# USB.net
KiCad netlist of a schematic drawn in Altium Designer
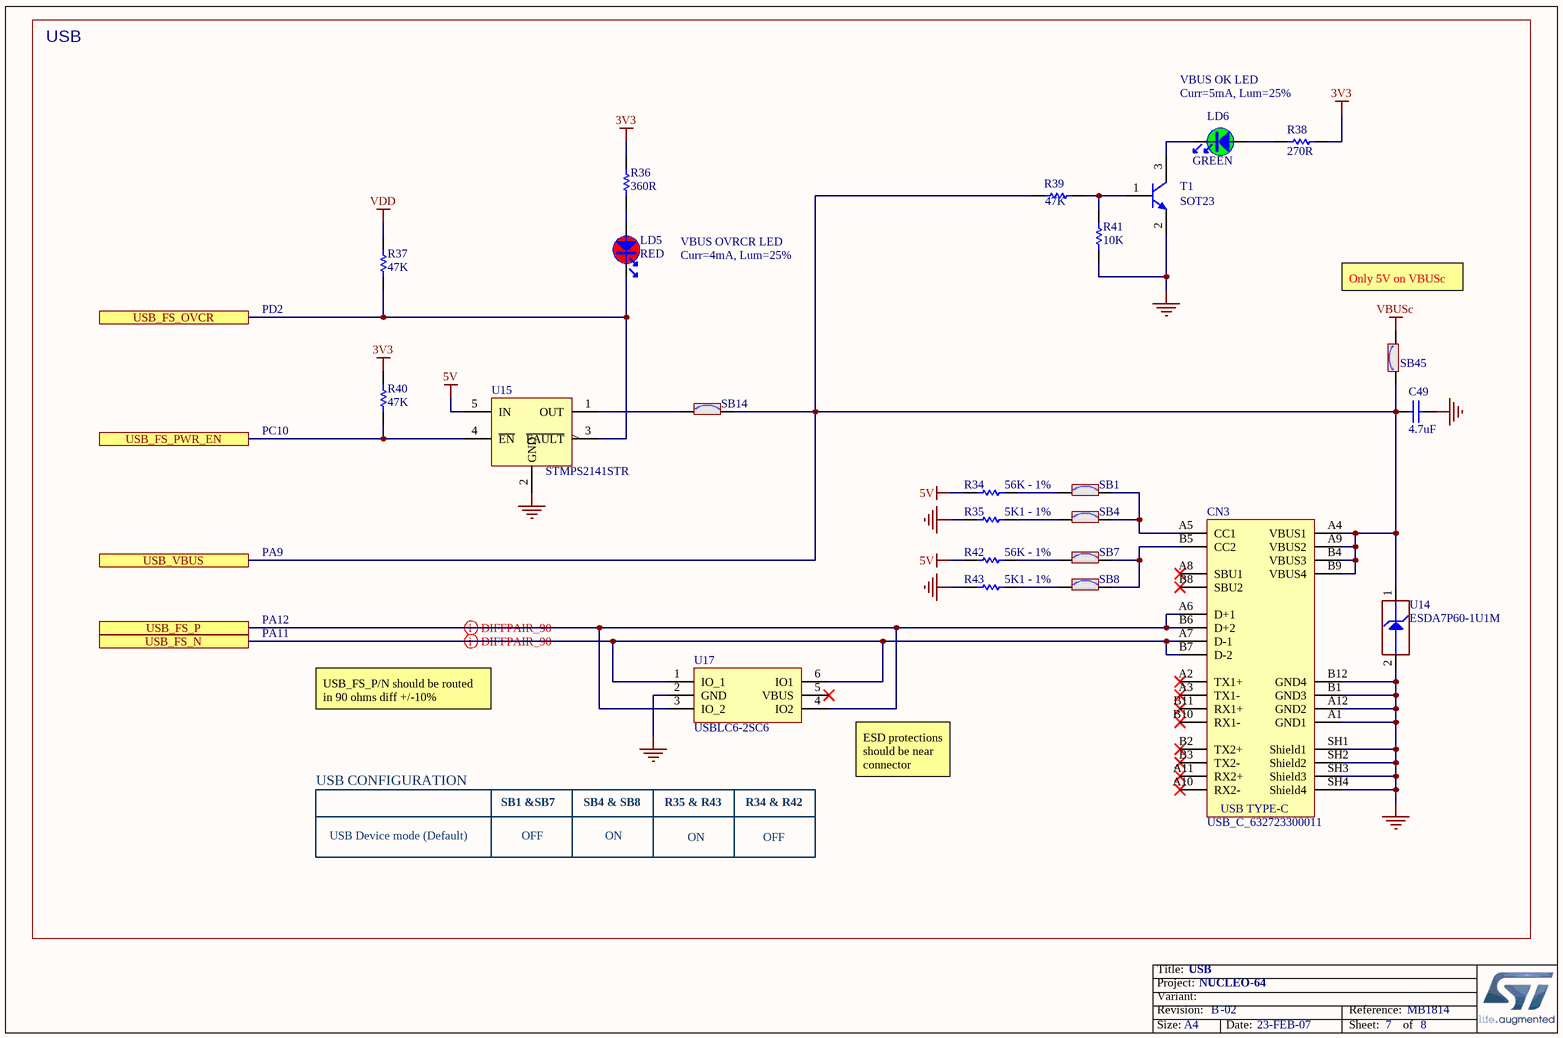
[diagram p0: USB.SchDoc]

(export (version "E")
  (design (tool "Eeschema 10.0.6"))
  (components
    (comp (ref "C49")
      (value "4.7uF")
      (footprint "C0603")
      (description "Capacitor, MLCC, 4.7uF, 16V, X5R, 10%, 0603, T=0.8mm")
      (fields
        (field (name "INTERNAL_PART_NUMBER") "MCD-00009")
        (field (name "MANUFACTURER_PART_NUMBER") "CC0603KRX5R7BB475")
        (field (name "PROVIDED_BY") "SUBCO")
      )
      (libsource (lib "MCD_PARTS_database") (part "Capacitor"))
    )
    (comp (ref "CN3")
      (value "USB_C_632723300011")
      (footprint "CON_USB-TYPEC_WE_632723300011")
      (description "USB_TypeC, 24pins, RA, TH, T=1.9mm (USB certified)")
      (fields
        (field (name "INTERNAL_PART_NUMBER") "MCD-02273")
        (field (name "MANUFACTURER") "WURTH ELEKTRONIK")
      )
      (libsource (lib "MCD_PARTS_database") (part "USB_TYPE_C_Receptacle"))
    )
    (comp (ref "LD5")
      (value "RED")
      (footprint "LED_0603_VISHAY_VLMS1300-GS08_RED_1A2K_H0P8")
      (description "LED Red, 0603 SMD, 2V Forward Voltage")
      (fields
        (field (name "INTERNAL_PART_NUMBER") "MCD-00587")
        (field (name "MANUFACTURER_PART_NUMBER") "VLMS1300-GS08")
        (field (name "PROVIDED_BY") "SUBCO")
      )
      (libsource (lib "MCD_PARTS_database") (part "LED_red"))
    )
    (comp (ref "LD6")
      (value "GREEN")
      (footprint "LED_0603_OSRAM_LG-Q396-PS-35_GREEN_1A2K_H0P4")
      (description "LED Green, 0603 SMD, Forward Voltage Typ=2V, Max=2.5V")
      (fields
        (field (name "INTERNAL_PART_NUMBER") "MCD-00588")
        (field (name "MANUFACTURER_PART_NUMBER") "LG Q396-PS-35")
        (field (name "PROVIDED_BY") "SUBCO")
      )
      (libsource (lib "MCD_PARTS_database") (part "LED_green"))
    )
    (comp (ref "R34")
      (value "56K - 1%")
      (footprint "R0603")
      (description "Resistor, 56K, 0603, +/-1%, 1/10W")
      (fields (field (name "INTERNAL_PART_NUMBER") "MCD-00494") (field (name "MANUFACTURER") "YAGEO"))
      (libsource (lib "MCD_PARTS_database") (part "Resistor"))
    )
    (comp (ref "R35")
      (value "5K1 - 1%")
      (footprint "R0603")
      (description "Resistor, 5K1, 0603, +/-1%, 1/10W")
      (fields (field (name "INTERNAL_PART_NUMBER") "MCD-00334") (field (name "MANUFACTURER") "YAGEO"))
      (libsource (lib "MCD_PARTS_database") (part "Resistor"))
    )
    (comp (ref "R36")
      (value "360R")
      (footprint "R0402")
      (description "Resistor,360R,0402,1%,1/16W")
      (fields
        (field (name "INTERNAL_PART_NUMBER") "MCD-00461")
        (field (name "MANUFACTURER_PART_NUMBER") "RC0402FR-07360RL")
        (field (name "PROVIDED_BY") "SUBCO")
      )
      (libsource (lib "MCD_PARTS_database") (part "Resistor"))
    )
    (comp (ref "R37")
      (value "47K")
      (footprint "R0402")
      (description "Resistor,47K,0402,1%,1/16W")
      (fields
        (field (name "INTERNAL_PART_NUMBER") "MCD-00063")
        (field (name "MANUFACTURER_PART_NUMBER") "RC0402FR-0747KL")
        (field (name "PROVIDED_BY") "SUBCO")
      )
      (libsource (lib "MCD_PARTS_database") (part "Resistor"))
    )
    (comp (ref "R38")
      (value "270R")
      (footprint "R0402")
      (description "Resistor,270R,0402,1%,1/16W")
      (fields
        (field (name "INTERNAL_PART_NUMBER") "MCD-00441")
        (field (name "MANUFACTURER_PART_NUMBER") "RC0402FR-07270RL")
        (field (name "PROVIDED_BY") "SUBCO")
      )
      (libsource (lib "MCD_PARTS_database") (part "Resistor"))
    )
    (comp (ref "R39")
      (value "47K")
      (footprint "R0402")
      (description "Resistor,47K,0402,1%,1/16W")
      (fields
        (field (name "INTERNAL_PART_NUMBER") "MCD-00063")
        (field (name "MANUFACTURER_PART_NUMBER") "RC0402FR-0747KL")
        (field (name "PROVIDED_BY") "SUBCO")
      )
      (libsource (lib "MCD_PARTS_database") (part "Resistor"))
    )
    (comp (ref "R40")
      (value "47K")
      (footprint "R0402")
      (description "Resistor,47K,0402,1%,1/16W")
      (fields
        (field (name "INTERNAL_PART_NUMBER") "MCD-00063")
        (field (name "MANUFACTURER_PART_NUMBER") "RC0402FR-0747KL")
        (field (name "PROVIDED_BY") "SUBCO")
      )
      (libsource (lib "MCD_PARTS_database") (part "Resistor"))
    )
    (comp (ref "R41")
      (value "10K")
      (footprint "R0402")
      (description "Resistor,10K,0402,1%,1/16W")
      (fields
        (field (name "INTERNAL_PART_NUMBER") "MCD-00053")
        (field (name "MANUFACTURER_PART_NUMBER") "RC0402FR-0710KL")
        (field (name "PROVIDED_BY") "SUBCO")
      )
      (libsource (lib "MCD_PARTS_database") (part "Resistor"))
    )
    (comp (ref "R42")
      (value "56K - 1%")
      (footprint "R0603")
      (description "Resistor, 56K, 0603, +/-1%, 1/10W")
      (fields (field (name "INTERNAL_PART_NUMBER") "MCD-00494") (field (name "MANUFACTURER") "YAGEO"))
      (libsource (lib "MCD_PARTS_database") (part "Resistor"))
    )
    (comp (ref "R43")
      (value "5K1 - 1%")
      (footprint "R0603")
      (description "Resistor, 5K1, 0603, +/-1%, 1/10W")
      (fields (field (name "INTERNAL_PART_NUMBER") "MCD-00334") (field (name "MANUFACTURER") "YAGEO"))
      (libsource (lib "MCD_PARTS_database") (part "Resistor"))
    )
    (comp (ref "SB1")
      (value "~")
      (footprint "SOLDER-BRIDGE_R0603-0R")
      (description "Solder Bridge ON")
      (fields
        (field (name "INTERNAL_PART_NUMBER") "MCD-00071")
        (field (name "MANUFACTURER_PART_NUMBER") "RC0603JR-070RL")
        (field (name "PROVIDED_BY") "SUBCO")
      )
      (libsource (lib "") (part "SB_ON_1"))
    )
    (comp (ref "SB4")
      (value "~")
      (footprint "SOLDER-BRIDGE_R0603-0R")
      (description "Solder Bridge ON")
      (fields
        (field (name "INTERNAL_PART_NUMBER") "MCD-00071")
        (field (name "MANUFACTURER_PART_NUMBER") "RC0603JR-070RL")
        (field (name "PROVIDED_BY") "SUBCO")
      )
      (libsource (lib "") (part "SB_ON_1"))
    )
    (comp (ref "SB7")
      (value "~")
      (footprint "SOLDER-BRIDGE_R0603-0R")
      (description "Solder Bridge ON")
      (fields
        (field (name "INTERNAL_PART_NUMBER") "MCD-00071")
        (field (name "MANUFACTURER_PART_NUMBER") "RC0603JR-070RL")
        (field (name "PROVIDED_BY") "SUBCO")
      )
      (libsource (lib "") (part "SB_ON_1"))
    )
    (comp (ref "SB8")
      (value "~")
      (footprint "SOLDER-BRIDGE_R0603-0R")
      (description "Solder Bridge ON")
      (fields
        (field (name "INTERNAL_PART_NUMBER") "MCD-00071")
        (field (name "MANUFACTURER_PART_NUMBER") "RC0603JR-070RL")
        (field (name "PROVIDED_BY") "SUBCO")
      )
      (libsource (lib "") (part "SB_ON_1"))
    )
    (comp (ref "SB14")
      (value "~")
      (footprint "SOLDER-BRIDGE_R0603-0R")
      (description "Solder Bridge ON")
      (fields
        (field (name "INTERNAL_PART_NUMBER") "MCD-00071")
        (field (name "MANUFACTURER_PART_NUMBER") "RC0603JR-070RL")
        (field (name "PROVIDED_BY") "SUBCO")
      )
      (libsource (lib "") (part "SB_ON_1"))
    )
    (comp (ref "SB45")
      (value "~")
      (footprint "SOLDER-BRIDGE_R0603-0R")
      (description "Solder Bridge ON")
      (fields
        (field (name "INTERNAL_PART_NUMBER") "MCD-00071")
        (field (name "MANUFACTURER_PART_NUMBER") "RC0603JR-070RL")
        (field (name "PROVIDED_BY") "SUBCO")
      )
      (libsource (lib "MCD_PARTS_database") (part "SB_ON"))
    )
    (comp (ref "T1")
      (value "SOT23")
      (footprint "NPN_SOT23")
      (description "NPN Bipolar Transistor")
      (fields
        (field (name "INTERNAL_PART_NUMBER") "MCD-00073")
        (field (name "MANUFACTURER_PART_NUMBER") "BSR14")
        (field (name "PROVIDED_BY") "SUBCO")
      )
      (libsource (lib "MCD_PARTS_database") (part "9013-SOT23"))
    )
    (comp (ref "U14")
      (value "ESDA7P60-1U1M")
      (footprint "ESD_QFN2_1P6X1_P125")
      (description "High power transient voltage suppressor, 7V breakdown")
      (fields (field (name "INTERNAL_PART_NUMBER") "MCD-00251") (field (name "BMS_PART_NUMBER") "9179042"))
      (libsource (lib "MCD_PARTS_database") (part "ESD-TRANSIL"))
    )
    (comp (ref "U15")
      (value "STMPS2141STR")
      (footprint "MOS_SOT23-5L")
      (description "Enhanced single channel power switches with active low enable pin")
      (fields
        (field (name "INTERNAL_PART_NUMBER") "MCD-00083")
        (field (name "MANUFACTURER") "STMICROELECTRONICS")
        (field (name "PROVIDED_BY") "SUBCO with ST control")
      )
      (libsource (lib "MCD_PARTS_database") (part "STMPS2141STR"))
    )
    (comp (ref "U17")
      (value "USBLC6-2SC6")
      (footprint "ESD_SOT23-6L")
      (description "Very low capacitance ESD protection")
      (fields
        (field (name "INTERNAL_PART_NUMBER") "MCD-00163")
        (field (name "MANUFACTURER") "STMICROELECTRONICS")
        (field (name "PROVIDED_BY") "SUBCO with ST control")
      )
      (libsource (lib "MCD_PARTS_database") (part "USBLC6-2SC6"))
    )
  )
  (nets
    (net (code "1") (name "/USB_FS_N") (class "Default")
      (node (ref "CN3") (pin "A7") (pinfunction "D-1_A7") (pintype "passive"))
      (node (ref "CN3") (pin "B7") (pinfunction "D-2_B7") (pintype "passive"))
      (node (ref "U17") (pin "1") (pinfunction "IO_1_1") (pintype "passive"))
      (node (ref "U17") (pin "6") (pinfunction "IO1_6") (pintype "passive"))
    )
    (net (code "2") (name "/USB_FS_OVCR") (class "Default")
      (node (ref "LD5") (pin "2") (pintype "passive"))
      (node (ref "R37") (pin "2") (pinfunction "2_2") (pintype "passive"))
      (node (ref "U15") (pin "3") (pinfunction "~{FAULT}_3") (pintype "passive"))
    )
    (net (code "3") (name "/USB_FS_P") (class "Default")
      (node (ref "CN3") (pin "A6") (pinfunction "D+1_A6") (pintype "passive"))
      (node (ref "CN3") (pin "B6") (pinfunction "D+2_B6") (pintype "passive"))
      (node (ref "U17") (pin "3") (pinfunction "IO_2_3") (pintype "passive"))
      (node (ref "U17") (pin "4") (pinfunction "IO2_4") (pintype "passive"))
    )
    (net (code "4") (name "/USB_FS_PWR_EN") (class "Default")
      (node (ref "R40") (pin "2") (pinfunction "2_2") (pintype "passive"))
      (node (ref "U15") (pin "4") (pinfunction "~{EN}_4") (pintype "passive"))
    )
    (net (code "5") (name "/USB_VBUS") (class "Default")
      (node (ref "C49") (pin "2") (pinfunction "2_2") (pintype "passive"))
      (node (ref "CN3") (pin "A4") (pinfunction "VBUS1_A4") (pintype "passive"))
      (node (ref "CN3") (pin "A9") (pinfunction "VBUS2_A9") (pintype "passive"))
      (node (ref "CN3") (pin "B4") (pinfunction "VBUS3_B4") (pintype "passive"))
      (node (ref "CN3") (pin "B9") (pinfunction "VBUS4_B9") (pintype "passive"))
      (node (ref "R39") (pin "1") (pinfunction "1_1") (pintype "passive"))
      (node (ref "SB14") (pin "2") (pinfunction "2_2") (pintype "passive"))
      (node (ref "SB45") (pin "1") (pinfunction "1_1") (pintype "passive"))
      (node (ref "U14") (pin "1") (pinfunction "IO1_1") (pintype "passive"))
    )
    (net (code "6") (name "3V3") (class "Default")
      (node (ref "R36") (pin "2") (pinfunction "2_2") (pintype "passive"))
      (node (ref "R38") (pin "2") (pinfunction "2_2") (pintype "passive"))
      (node (ref "R40") (pin "1") (pinfunction "1_1") (pintype "passive"))
    )
    (net (code "7") (name "5V") (class "Default")
      (node (ref "R34") (pin "1") (pinfunction "1_1") (pintype "passive"))
      (node (ref "R42") (pin "1") (pinfunction "1_1") (pintype "passive"))
      (node (ref "U15") (pin "5") (pinfunction "IN_5") (pintype "passive"))
    )
    (net (code "8") (name "GND") (class "Default")
      (node (ref "C49") (pin "1") (pinfunction "1_1") (pintype "passive"))
      (node (ref "CN3") (pin "A1") (pinfunction "GND1_A1") (pintype "passive"))
      (node (ref "CN3") (pin "A12") (pinfunction "GND2_A12") (pintype "passive"))
      (node (ref "CN3") (pin "B1") (pinfunction "GND3_B1") (pintype "passive"))
      (node (ref "CN3") (pin "B12") (pinfunction "GND4_B12") (pintype "passive"))
      (node (ref "CN3") (pin "SH1") (pinfunction "Shield1_SH1") (pintype "passive"))
      (node (ref "CN3") (pin "SH2") (pinfunction "Shield2_SH2") (pintype "passive"))
      (node (ref "CN3") (pin "SH3") (pinfunction "Shield3_SH3") (pintype "passive"))
      (node (ref "CN3") (pin "SH4") (pinfunction "Shield4_SH4") (pintype "passive"))
      (node (ref "R35") (pin "1") (pinfunction "1_1") (pintype "passive"))
      (node (ref "R41") (pin "1") (pinfunction "1_1") (pintype "passive"))
      (node (ref "R43") (pin "1") (pinfunction "1_1") (pintype "passive"))
      (node (ref "T1") (pin "2") (pinfunction "E_2") (pintype "passive"))
      (node (ref "U14") (pin "2") (pinfunction "GND_2") (pintype "passive"))
      (node (ref "U15") (pin "2") (pinfunction "GND_2") (pintype "passive"))
      (node (ref "U17") (pin "2") (pinfunction "GND_2") (pintype "passive"))
    )
    (net (code "9") (name "Net-(CN3-CC1)") (class "Default")
      (node (ref "CN3") (pin "A5") (pinfunction "CC1_A5") (pintype "passive"))
      (node (ref "SB1") (pin "2") (pinfunction "2_2") (pintype "passive"))
      (node (ref "SB4") (pin "2") (pinfunction "2_2") (pintype "passive"))
    )
    (net (code "10") (name "Net-(CN3-CC2)") (class "Default")
      (node (ref "CN3") (pin "B5") (pinfunction "CC2_B5") (pintype "passive"))
      (node (ref "SB7") (pin "2") (pinfunction "2_2") (pintype "passive"))
      (node (ref "SB8") (pin "2") (pinfunction "2_2") (pintype "passive"))
    )
    (net (code "11") (name "Net-(LD5-Pad1)") (class "Default")
      (node (ref "LD5") (pin "1") (pintype "passive"))
      (node (ref "R36") (pin "1") (pinfunction "1_1") (pintype "passive"))
    )
    (net (code "12") (name "Net-(LD6-Pad1)") (class "Default")
      (node (ref "LD6") (pin "1") (pintype "passive"))
      (node (ref "R38") (pin "1") (pinfunction "1_1") (pintype "passive"))
    )
    (net (code "13") (name "Net-(R34-Pad2)") (class "Default")
      (node (ref "R34") (pin "2") (pinfunction "2_2") (pintype "passive"))
      (node (ref "SB1") (pin "1") (pinfunction "1_1") (pintype "passive"))
    )
    (net (code "14") (name "Net-(R35-Pad2)") (class "Default")
      (node (ref "R35") (pin "2") (pinfunction "2_2") (pintype "passive"))
      (node (ref "SB4") (pin "1") (pinfunction "1_1") (pintype "passive"))
    )
    (net (code "15") (name "Net-(R42-Pad2)") (class "Default")
      (node (ref "R42") (pin "2") (pinfunction "2_2") (pintype "passive"))
      (node (ref "SB7") (pin "1") (pinfunction "1_1") (pintype "passive"))
    )
    (net (code "16") (name "Net-(R43-Pad2)") (class "Default")
      (node (ref "R43") (pin "2") (pinfunction "2_2") (pintype "passive"))
      (node (ref "SB8") (pin "1") (pinfunction "1_1") (pintype "passive"))
    )
    (net (code "17") (name "Net-(T1-B)") (class "Default")
      (node (ref "R39") (pin "2") (pinfunction "2_2") (pintype "passive"))
      (node (ref "R41") (pin "2") (pinfunction "2_2") (pintype "passive"))
      (node (ref "T1") (pin "1") (pinfunction "B_1") (pintype "passive"))
    )
    (net (code "18") (name "Net-(T1-C)") (class "Default")
      (node (ref "LD6") (pin "2") (pintype "passive"))
      (node (ref "T1") (pin "3") (pinfunction "C_3") (pintype "passive"))
    )
    (net (code "19") (name "Net-(U15-OUT)") (class "Default")
      (node (ref "SB14") (pin "1") (pinfunction "1_1") (pintype "passive"))
      (node (ref "U15") (pin "1") (pinfunction "OUT_1") (pintype "passive"))
    )
    (net (code "20") (name "VBUSc") (class "Default")
      (node (ref "SB45") (pin "2") (pinfunction "2_2") (pintype "passive"))
    )
    (net (code "21") (name "VDD") (class "Default")
      (node (ref "R37") (pin "1") (pinfunction "1_1") (pintype "passive"))
    )
    (net (code "22") (name "unconnected-(CN3-RX1+-PadB11)") (class "Default")
      (node (ref "CN3") (pin "B11") (pinfunction "RX1+_B11") (pintype "passive+no_connect"))
    )
    (net (code "23") (name "unconnected-(CN3-RX1--PadB10)") (class "Default")
      (node (ref "CN3") (pin "B10") (pinfunction "RX1-_B10") (pintype "passive+no_connect"))
    )
    (net (code "24") (name "unconnected-(CN3-RX2+-PadA11)") (class "Default")
      (node (ref "CN3") (pin "A11") (pinfunction "RX2+_A11") (pintype "passive+no_connect"))
    )
    (net (code "25") (name "unconnected-(CN3-RX2--PadA10)") (class "Default")
      (node (ref "CN3") (pin "A10") (pinfunction "RX2-_A10") (pintype "passive+no_connect"))
    )
    (net (code "26") (name "unconnected-(CN3-SBU1-PadA8)") (class "Default")
      (node (ref "CN3") (pin "A8") (pinfunction "SBU1_A8") (pintype "passive+no_connect"))
    )
    (net (code "27") (name "unconnected-(CN3-SBU2-PadB8)") (class "Default")
      (node (ref "CN3") (pin "B8") (pinfunction "SBU2_B8") (pintype "passive+no_connect"))
    )
    (net (code "28") (name "unconnected-(CN3-TX1+-PadA2)") (class "Default")
      (node (ref "CN3") (pin "A2") (pinfunction "TX1+_A2") (pintype "passive+no_connect"))
    )
    (net (code "29") (name "unconnected-(CN3-TX1--PadA3)") (class "Default")
      (node (ref "CN3") (pin "A3") (pinfunction "TX1-_A3") (pintype "passive+no_connect"))
    )
    (net (code "30") (name "unconnected-(CN3-TX2+-PadB2)") (class "Default")
      (node (ref "CN3") (pin "B2") (pinfunction "TX2+_B2") (pintype "passive+no_connect"))
    )
    (net (code "31") (name "unconnected-(CN3-TX2--PadB3)") (class "Default")
      (node (ref "CN3") (pin "B3") (pinfunction "TX2-_B3") (pintype "passive+no_connect"))
    )
    (net (code "32") (name "unconnected-(U17-VBUS-Pad5)") (class "Default")
      (node (ref "U17") (pin "5") (pinfunction "VBUS_5") (pintype "passive+no_connect"))
    )
  )
)
